# DisplayCarrierFlipped.net
KiCad netlist of a schematic drawn in EAGLE
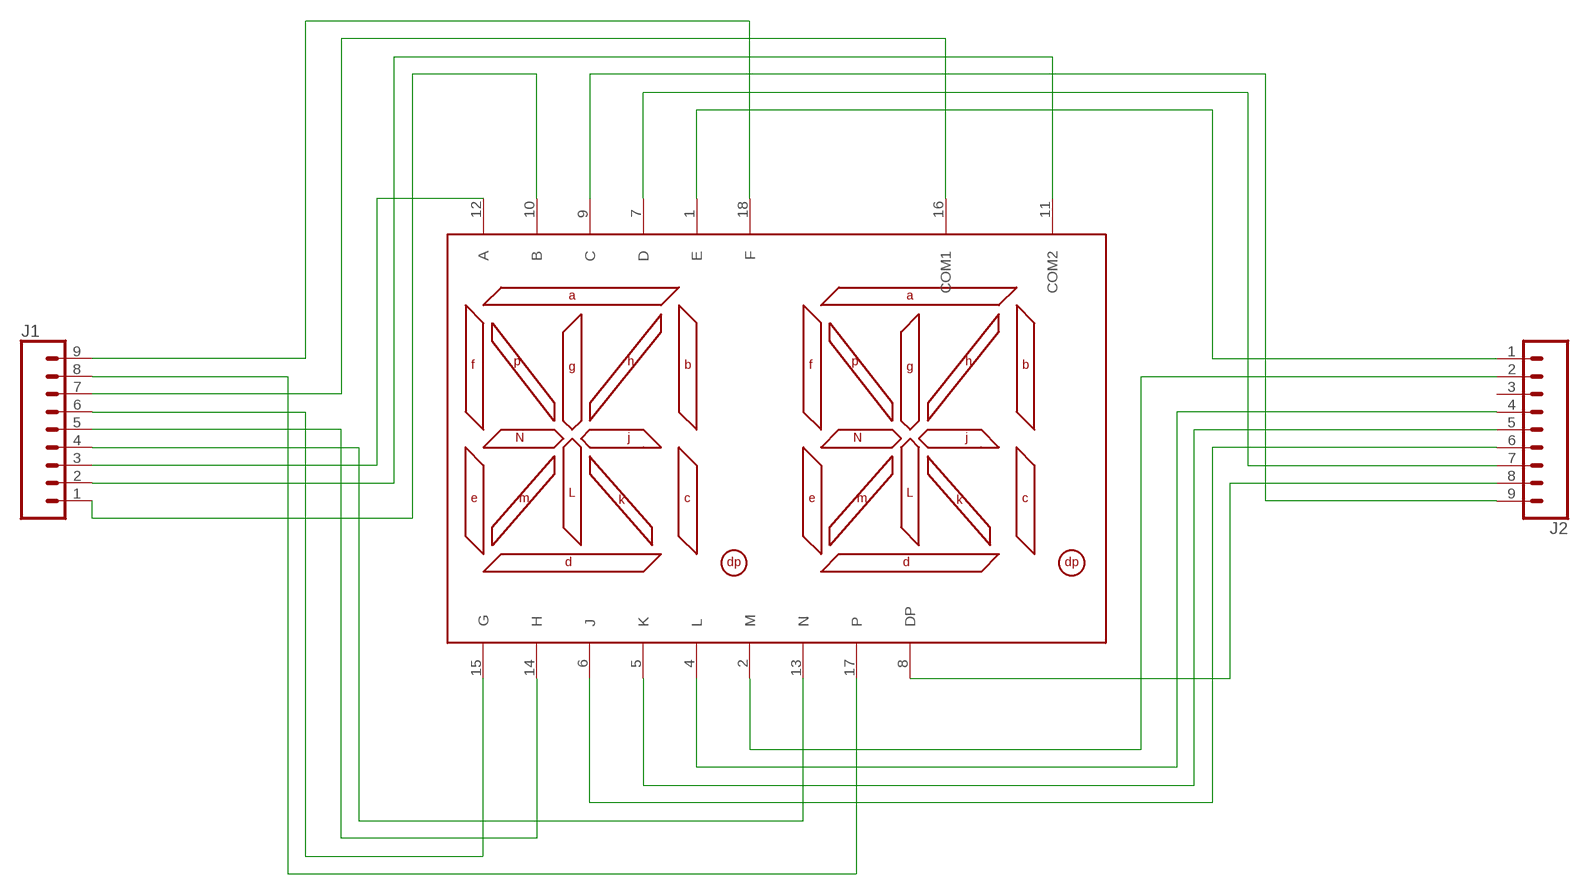
[diagram p0: schematic, sheet 1]

(export (version "E")
  (design (tool "Eeschema 10.0.6"))
  (components
    (comp (ref "J1")
      (value "CONN_09")
      (footprint "eagle-import:1X09")
      (libsource (lib "eagle-import") (part "CONN_09"))
    )
    (comp (ref "J2")
      (value "CONN_09")
      (footprint "eagle-import:1X09")
      (libsource (lib "eagle-import") (part "CONN_09"))
    )
    (comp (ref "U$1")
      (value "HDSP-A27C")
      (footprint "eagle-import:DIP-18")
      (libsource (lib "eagle-import") (part "HDSP-A27C"))
    )
  )
  (nets
    (net (code "1") (name "Net-(U$1-A)") (class "Default")
      (node (ref "J1") (pin "3") (pinfunction "3_3") (pintype "passive"))
      (node (ref "U$1") (pin "12") (pinfunction "A_12") (pintype "bidirectional"))
    )
    (net (code "2") (name "Net-(U$1-B)") (class "Default")
      (node (ref "J1") (pin "1") (pinfunction "1_1") (pintype "passive"))
      (node (ref "U$1") (pin "10") (pinfunction "B_10") (pintype "bidirectional"))
    )
    (net (code "3") (name "Net-(U$1-C)") (class "Default")
      (node (ref "J2") (pin "9") (pinfunction "9_9") (pintype "passive"))
      (node (ref "U$1") (pin "9") (pinfunction "C_9") (pintype "bidirectional"))
    )
    (net (code "4") (name "Net-(U$1-COM1)") (class "Default")
      (node (ref "J1") (pin "7") (pinfunction "7_7") (pintype "passive"))
      (node (ref "U$1") (pin "16") (pinfunction "COM1_16") (pintype "bidirectional"))
    )
    (net (code "5") (name "Net-(U$1-COM2)") (class "Default")
      (node (ref "J1") (pin "2") (pinfunction "2_2") (pintype "passive"))
      (node (ref "U$1") (pin "11") (pinfunction "COM2_11") (pintype "bidirectional"))
    )
    (net (code "6") (name "Net-(U$1-D)") (class "Default")
      (node (ref "J2") (pin "7") (pinfunction "7_7") (pintype "passive"))
      (node (ref "U$1") (pin "7") (pinfunction "D_7") (pintype "bidirectional"))
    )
    (net (code "7") (name "Net-(U$1-DP)") (class "Default")
      (node (ref "J2") (pin "8") (pinfunction "8_8") (pintype "passive"))
      (node (ref "U$1") (pin "8") (pinfunction "DP_8") (pintype "bidirectional"))
    )
    (net (code "8") (name "Net-(U$1-E)") (class "Default")
      (node (ref "J2") (pin "1") (pinfunction "1_1") (pintype "passive"))
      (node (ref "U$1") (pin "1") (pinfunction "E_1") (pintype "bidirectional"))
    )
    (net (code "9") (name "Net-(U$1-F)") (class "Default")
      (node (ref "J1") (pin "9") (pinfunction "9_9") (pintype "passive"))
      (node (ref "U$1") (pin "18") (pinfunction "F_18") (pintype "bidirectional"))
    )
    (net (code "10") (name "Net-(U$1-G)") (class "Default")
      (node (ref "J1") (pin "6") (pinfunction "6_6") (pintype "passive"))
      (node (ref "U$1") (pin "15") (pinfunction "G_15") (pintype "bidirectional"))
    )
    (net (code "11") (name "Net-(U$1-H)") (class "Default")
      (node (ref "J1") (pin "5") (pinfunction "5_5") (pintype "passive"))
      (node (ref "U$1") (pin "14") (pinfunction "H_14") (pintype "bidirectional"))
    )
    (net (code "12") (name "Net-(U$1-J)") (class "Default")
      (node (ref "J2") (pin "6") (pinfunction "6_6") (pintype "passive"))
      (node (ref "U$1") (pin "6") (pinfunction "J_6") (pintype "bidirectional"))
    )
    (net (code "13") (name "Net-(U$1-K)") (class "Default")
      (node (ref "J2") (pin "5") (pinfunction "5_5") (pintype "passive"))
      (node (ref "U$1") (pin "5") (pinfunction "K_5") (pintype "bidirectional"))
    )
    (net (code "14") (name "Net-(U$1-L)") (class "Default")
      (node (ref "J2") (pin "4") (pinfunction "4_4") (pintype "passive"))
      (node (ref "U$1") (pin "4") (pinfunction "L_4") (pintype "bidirectional"))
    )
    (net (code "15") (name "Net-(U$1-M)") (class "Default")
      (node (ref "J2") (pin "2") (pinfunction "2_2") (pintype "passive"))
      (node (ref "U$1") (pin "2") (pinfunction "M_2") (pintype "bidirectional"))
    )
    (net (code "16") (name "Net-(U$1-N)") (class "Default")
      (node (ref "J1") (pin "4") (pinfunction "4_4") (pintype "passive"))
      (node (ref "U$1") (pin "13") (pinfunction "N_13") (pintype "bidirectional"))
    )
    (net (code "17") (name "Net-(U$1-P)") (class "Default")
      (node (ref "J1") (pin "8") (pinfunction "8_8") (pintype "passive"))
      (node (ref "U$1") (pin "17") (pinfunction "P_17") (pintype "bidirectional"))
    )
    (net (code "18") (name "unconnected-(J2-Pad3)") (class "Default")
      (node (ref "J2") (pin "3") (pinfunction "3_3") (pintype "passive"))
    )
  )
)
